# PowerMonitorV2.net
KiCad netlist of a schematic drawn in EAGLE
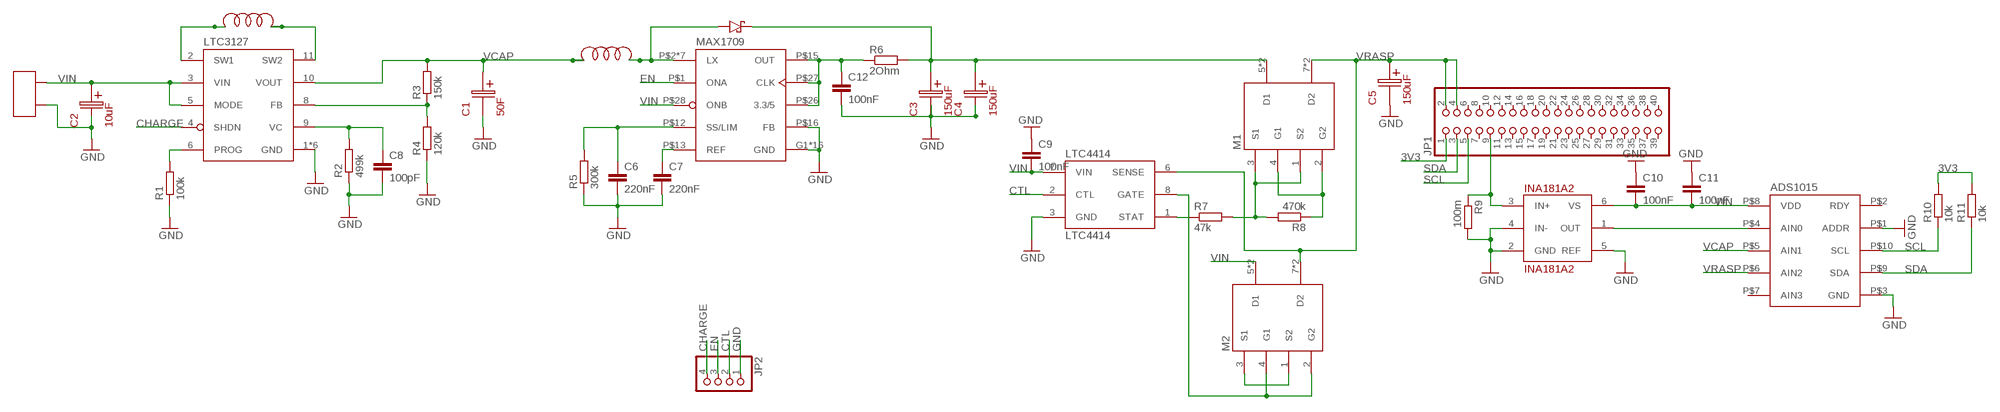
[diagram p0: schematic, sheet 1]

(export (version "E")
  (design (tool "Eeschema 10.0.6"))
  (components
    (comp (ref "ADS1015")
      (value "ADS1015")
      (footprint "eagle-import:VSSOP-10")
      (libsource (lib "eagle-import") (part "ADS1015"))
    )
    (comp (ref "C1")
      (value "50F")
      (footprint "eagle-import:CAP_RAD_8MM")
      (libsource (lib "eagle-import") (part "CAPACITOR8MM50F_SUPERCAP"))
    )
    (comp (ref "C2")
      (value "10uF")
      (footprint "eagle-import:CAP_RAD_2.5MM")
      (libsource (lib "eagle-import") (part "CAPACITOR2.5MM"))
    )
    (comp (ref "C3")
      (value "150uF")
      (footprint "eagle-import:CAP_RAD_3.5MM")
      (libsource (lib "eagle-import") (part "CAPACITOR3.5MM"))
    )
    (comp (ref "C4")
      (value "150uF")
      (footprint "eagle-import:CAP_RAD_3.5MM")
      (libsource (lib "eagle-import") (part "CAPACITOR3.5MM"))
    )
    (comp (ref "C5")
      (value "150uF")
      (footprint "eagle-import:CAP_RAD_3.5MM")
      (libsource (lib "eagle-import") (part "CAPACITOR3.5MM"))
    )
    (comp (ref "C6")
      (value "220nF")
      (footprint "eagle-import:C0805")
      (libsource (lib "eagle-import") (part "C-EUC0805"))
    )
    (comp (ref "C7")
      (value "220nF")
      (footprint "eagle-import:C0805")
      (libsource (lib "eagle-import") (part "C-EUC0805"))
    )
    (comp (ref "C8")
      (value "100pF")
      (footprint "eagle-import:C0805")
      (libsource (lib "eagle-import") (part "C-EUC0805"))
    )
    (comp (ref "C9")
      (value "100nF")
      (footprint "eagle-import:C0805")
      (libsource (lib "eagle-import") (part "C-EUC0805"))
    )
    (comp (ref "C10")
      (value "100nF")
      (footprint "eagle-import:C0805")
      (libsource (lib "eagle-import") (part "C-EUC0805"))
    )
    (comp (ref "C11")
      (value "100nF")
      (footprint "eagle-import:C0805")
      (libsource (lib "eagle-import") (part "C-EUC0805"))
    )
    (comp (ref "C12")
      (value "100nF")
      (footprint "eagle-import:C0805")
      (libsource (lib "eagle-import") (part "C-EUC0805"))
    )
    (comp (ref "CON1")
      (value "TERM-2")
      (footprint "eagle-import:TERM-2")
      (libsource (lib "eagle-import") (part "TERM-2"))
    )
    (comp (ref "D1")
      (value "STPS8L30_DPAK")
      (footprint "eagle-import:DPAK")
      (libsource (lib "eagle-import") (part "STPS8L30_DPAK"))
    )
    (comp (ref "INA181A2")
      (value "INA181A2")
      (footprint "eagle-import:SOT-23-6")
      (libsource (lib "eagle-import") (part "INA181A2"))
    )
    (comp (ref "JP1")
      (value "PINHD-2X20")
      (footprint "eagle-import:2X20")
      (libsource (lib "eagle-import") (part "PINHD-2X20"))
    )
    (comp (ref "JP2")
      (value "PINHD-1X4/90")
      (footprint "eagle-import:1X04_90")
      (libsource (lib "eagle-import") (part "PINHD-1X4/90"))
    )
    (comp (ref "L1")
      (value "4.7uH")
      (footprint "eagle-import:IND6X6")
      (libsource (lib "eagle-import") (part "INDUCTOR6MM"))
    )
    (comp (ref "L2")
      (value "1uH")
      (footprint "eagle-import:IND6X6")
      (libsource (lib "eagle-import") (part "INDUCTOR6MM"))
    )
    (comp (ref "LTC3127")
      (value "LTC3127")
      (footprint "eagle-import:MS-12E2")
      (libsource (lib "eagle-import") (part "LTC3127"))
    )
    (comp (ref "LTC4414")
      (value "LTC4414")
      (footprint "eagle-import:MS8")
      (libsource (lib "eagle-import") (part "LTC4414"))
    )
    (comp (ref "M1")
      (value "IRF9358PBF")
      (footprint "eagle-import:SO-8")
      (libsource (lib "eagle-import") (part "IRF9358PBF"))
    )
    (comp (ref "M2")
      (value "IRF9358PBF")
      (footprint "eagle-import:SO-8")
      (libsource (lib "eagle-import") (part "IRF9358PBF"))
    )
    (comp (ref "MAX1709")
      (value "MAX1709")
      (footprint "eagle-import:TSSOP-EP28")
      (libsource (lib "eagle-import") (part "MAX1709"))
    )
    (comp (ref "R1")
      (value "100k")
      (footprint "eagle-import:R0805")
      (libsource (lib "eagle-import") (part "R-EU_R0805"))
    )
    (comp (ref "R2")
      (value "499k")
      (footprint "eagle-import:R0805")
      (libsource (lib "eagle-import") (part "R-EU_R0805"))
    )
    (comp (ref "R3")
      (value "150k")
      (footprint "eagle-import:R0805")
      (libsource (lib "eagle-import") (part "R-EU_R0805"))
    )
    (comp (ref "R4")
      (value "120k")
      (footprint "eagle-import:R0805")
      (libsource (lib "eagle-import") (part "R-EU_R0805"))
    )
    (comp (ref "R5")
      (value "300k")
      (footprint "eagle-import:R0805")
      (libsource (lib "eagle-import") (part "R-EU_R0805"))
    )
    (comp (ref "R6")
      (value "2Ohm")
      (footprint "eagle-import:R0805")
      (libsource (lib "eagle-import") (part "R-EU_R0805"))
    )
    (comp (ref "R7")
      (value "47k")
      (footprint "eagle-import:R0805")
      (libsource (lib "eagle-import") (part "R-EU_R0805"))
    )
    (comp (ref "R8")
      (value "470k")
      (footprint "eagle-import:R0805")
      (libsource (lib "eagle-import") (part "R-EU_R0805"))
    )
    (comp (ref "R9")
      (value "100m")
      (footprint "eagle-import:R0805")
      (libsource (lib "eagle-import") (part "R-EU_R0805"))
    )
    (comp (ref "R10")
      (value "10k")
      (footprint "eagle-import:R0805")
      (libsource (lib "eagle-import") (part "R-EU_R0805"))
    )
    (comp (ref "R11")
      (value "10k")
      (footprint "eagle-import:R0805")
      (libsource (lib "eagle-import") (part "R-EU_R0805"))
    )
  )
  (nets
    (net (code "1") (name "/3V3") (class "Default")
      (node (ref "JP1") (pin "1") (pinfunction "1_1") (pintype "passive"))
      (node (ref "R10") (pin "2") (pinfunction "2_2") (pintype "passive"))
      (node (ref "R11") (pin "2") (pinfunction "2_2") (pintype "passive"))
    )
    (net (code "2") (name "/CHARGE") (class "Default")
      (node (ref "JP2") (pin "4") (pinfunction "4_4") (pintype "passive"))
      (node (ref "LTC3127") (pin "4") (pinfunction "SHDN_4") (pintype "bidirectional"))
    )
    (net (code "3") (name "/CTL") (class "Default")
      (node (ref "JP2") (pin "2") (pinfunction "2_2") (pintype "passive"))
      (node (ref "LTC4414") (pin "2") (pinfunction "CTL_2") (pintype "bidirectional"))
    )
    (net (code "4") (name "/EN") (class "Default")
      (node (ref "JP2") (pin "3") (pinfunction "3_3") (pintype "passive"))
      (node (ref "MAX1709") (pin "P$1") (pinfunction "ONA_P$1") (pintype "bidirectional"))
    )
    (net (code "5") (name "/SCL") (class "Default")
      (node (ref "ADS1015") (pin "P$10") (pinfunction "SCL_P$10") (pintype "bidirectional"))
      (node (ref "JP1") (pin "5") (pinfunction "5_5") (pintype "passive"))
      (node (ref "R10") (pin "1") (pinfunction "1_1") (pintype "passive"))
    )
    (net (code "6") (name "/SDA") (class "Default")
      (node (ref "ADS1015") (pin "P$9") (pinfunction "SDA_P$9") (pintype "bidirectional"))
      (node (ref "JP1") (pin "3") (pinfunction "3_3") (pintype "passive"))
      (node (ref "R11") (pin "1") (pinfunction "1_1") (pintype "passive"))
    )
    (net (code "7") (name "/VCAP") (class "Default")
      (node (ref "ADS1015") (pin "P$5") (pinfunction "AIN1_P$5") (pintype "bidirectional"))
      (node (ref "C1") (pin "VCAP") (pinfunction "V+_VCAP") (pintype "power_in"))
      (node (ref "L2") (pin "P$1") (pinfunction "P$1_P$1") (pintype "bidirectional"))
      (node (ref "L2") (pin "P$3") (pinfunction "P$1_P$3") (pintype "bidirectional"))
      (node (ref "L2") (pin "P$4") (pinfunction "P$1_P$4") (pintype "bidirectional"))
      (node (ref "LTC3127") (pin "10") (pinfunction "VOUT_10") (pintype "bidirectional"))
      (node (ref "R3") (pin "2") (pinfunction "2_2") (pintype "passive"))
    )
    (net (code "8") (name "/VIN") (class "Default")
      (node (ref "ADS1015") (pin "P$8") (pinfunction "VDD_P$8") (pintype "bidirectional"))
      (node (ref "C10") (pin "2") (pinfunction "2_2") (pintype "passive"))
      (node (ref "C11") (pin "2") (pinfunction "2_2") (pintype "passive"))
      (node (ref "C2") (pin "VCAP") (pinfunction "V+_VCAP") (pintype "power_in"))
      (node (ref "C9") (pin "2") (pinfunction "2_2") (pintype "passive"))
      (node (ref "CON1") (pin "1") (pinfunction "P$1_1") (pintype "bidirectional"))
      (node (ref "INA181A2") (pin "6") (pinfunction "VS_6") (pintype "power_in"))
      (node (ref "LTC3127") (pin "3") (pinfunction "VIN_3") (pintype "bidirectional"))
      (node (ref "LTC3127") (pin "5") (pinfunction "MODE_5") (pintype "bidirectional"))
      (node (ref "LTC4414") (pin "7") (pinfunction "VIN_7") (pintype "bidirectional"))
      (node (ref "M2") (pin "5") (pinfunction "D1_5") (pintype "bidirectional"))
      (node (ref "M2") (pin "6") (pinfunction "D1_6") (pintype "bidirectional"))
      (node (ref "MAX1709") (pin "P$28") (pinfunction "ONB_P$28") (pintype "bidirectional"))
    )
    (net (code "9") (name "/VRASP") (class "Default")
      (node (ref "ADS1015") (pin "P$6") (pinfunction "AIN2_P$6") (pintype "bidirectional"))
      (node (ref "C5") (pin "VCAP") (pinfunction "V+_VCAP") (pintype "power_in"))
      (node (ref "JP1") (pin "2") (pinfunction "2_2") (pintype "passive"))
      (node (ref "JP1") (pin "4") (pinfunction "4_4") (pintype "passive"))
      (node (ref "LTC4414") (pin "6") (pinfunction "SENSE_6") (pintype "bidirectional"))
      (node (ref "M1") (pin "7") (pinfunction "D2_7") (pintype "bidirectional"))
      (node (ref "M1") (pin "8") (pinfunction "D2_8") (pintype "bidirectional"))
      (node (ref "M2") (pin "7") (pinfunction "D2_7") (pintype "bidirectional"))
      (node (ref "M2") (pin "8") (pinfunction "D2_8") (pintype "bidirectional"))
    )
    (net (code "10") (name "GND") (class "Default")
      (node (ref "ADS1015") (pin "P$1") (pinfunction "ADDR_P$1") (pintype "bidirectional"))
      (node (ref "ADS1015") (pin "P$3") (pinfunction "GND_P$3") (pintype "bidirectional"))
      (node (ref "C1") (pin "GND") (pinfunction "V-_GND") (pintype "power_in"))
      (node (ref "C10") (pin "1") (pinfunction "1_1") (pintype "passive"))
      (node (ref "C11") (pin "1") (pinfunction "1_1") (pintype "passive"))
      (node (ref "C12") (pin "2") (pinfunction "2_2") (pintype "passive"))
      (node (ref "C2") (pin "GND") (pinfunction "V-_GND") (pintype "power_in"))
      (node (ref "C3") (pin "GND") (pinfunction "V-_GND") (pintype "power_in"))
      (node (ref "C4") (pin "GND") (pinfunction "V-_GND") (pintype "power_in"))
      (node (ref "C5") (pin "GND") (pinfunction "V-_GND") (pintype "power_in"))
      (node (ref "C6") (pin "2") (pinfunction "2_2") (pintype "passive"))
      (node (ref "C7") (pin "2") (pinfunction "2_2") (pintype "passive"))
      (node (ref "C8") (pin "2") (pinfunction "2_2") (pintype "passive"))
      (node (ref "C9") (pin "1") (pinfunction "1_1") (pintype "passive"))
      (node (ref "CON1") (pin "2") (pinfunction "P$2_2") (pintype "bidirectional"))
      (node (ref "INA181A2") (pin "2") (pinfunction "GND_2") (pintype "power_in"))
      (node (ref "INA181A2") (pin "4") (pinfunction "IN-_4") (pintype "input"))
      (node (ref "INA181A2") (pin "5") (pinfunction "REF_5") (pintype "input"))
      (node (ref "JP2") (pin "1") (pinfunction "1_1") (pintype "passive"))
      (node (ref "LTC3127") (pin "1") (pinfunction "GND_1") (pintype "bidirectional"))
      (node (ref "LTC3127") (pin "12") (pinfunction "GND_12") (pintype "bidirectional"))
      (node (ref "LTC3127") (pin "13_0") (pinfunction "GND_13_0") (pintype "bidirectional"))
      (node (ref "LTC3127") (pin "13_1") (pinfunction "GND_13_1") (pintype "bidirectional"))
      (node (ref "LTC3127") (pin "13_2") (pinfunction "GND_13_2") (pintype "bidirectional"))
      (node (ref "LTC3127") (pin "7") (pinfunction "GND_7") (pintype "bidirectional"))
      (node (ref "LTC4414") (pin "3") (pinfunction "GND_3") (pintype "bidirectional"))
      (node (ref "MAX1709") (pin "G1") (pinfunction "GND_G1") (pintype "bidirectional"))
      (node (ref "MAX1709") (pin "G2") (pinfunction "GND_G2") (pintype "bidirectional"))
      (node (ref "MAX1709") (pin "G3") (pinfunction "GND_G3") (pintype "bidirectional"))
      (node (ref "MAX1709") (pin "G4") (pinfunction "GND_G4") (pintype "bidirectional"))
      (node (ref "MAX1709") (pin "G5") (pinfunction "GND_G5") (pintype "bidirectional"))
      (node (ref "MAX1709") (pin "G6") (pinfunction "GND_G6") (pintype "bidirectional"))
      (node (ref "MAX1709") (pin "G7") (pinfunction "GND_G7") (pintype "bidirectional"))
      (node (ref "MAX1709") (pin "G8") (pinfunction "GND_G8") (pintype "bidirectional"))
      (node (ref "MAX1709") (pin "P$11") (pinfunction "GND_P$11") (pintype "bidirectional"))
      (node (ref "MAX1709") (pin "P$14") (pinfunction "GND_P$14") (pintype "bidirectional"))
      (node (ref "MAX1709") (pin "P$16") (pinfunction "FB_P$16") (pintype "bidirectional"))
      (node (ref "MAX1709") (pin "P$18") (pinfunction "GND_P$18") (pintype "bidirectional"))
      (node (ref "MAX1709") (pin "P$19") (pinfunction "GND_P$19") (pintype "bidirectional"))
      (node (ref "MAX1709") (pin "P$20") (pinfunction "GND_P$20") (pintype "bidirectional"))
      (node (ref "MAX1709") (pin "P$21") (pinfunction "GND_P$21") (pintype "bidirectional"))
      (node (ref "MAX1709") (pin "P$22") (pinfunction "GND_P$22") (pintype "bidirectional"))
      (node (ref "MAX1709") (pin "P$23") (pinfunction "GND_P$23") (pintype "bidirectional"))
      (node (ref "R1") (pin "1") (pinfunction "1_1") (pintype "passive"))
      (node (ref "R2") (pin "1") (pinfunction "1_1") (pintype "passive"))
      (node (ref "R4") (pin "1") (pinfunction "1_1") (pintype "passive"))
      (node (ref "R5") (pin "1") (pinfunction "1_1") (pintype "passive"))
      (node (ref "R9") (pin "2") (pinfunction "2_2") (pintype "passive"))
    )
    (net (code "11") (name "Net-(ADS1015-AIN0)") (class "Default")
      (node (ref "ADS1015") (pin "P$4") (pinfunction "AIN0_P$4") (pintype "bidirectional"))
      (node (ref "INA181A2") (pin "1") (pinfunction "OUT_1") (pintype "output"))
    )
    (net (code "12") (name "Net-(C3-V+)") (class "Default")
      (node (ref "C3") (pin "VCAP") (pinfunction "V+_VCAP") (pintype "power_in"))
      (node (ref "C4") (pin "VCAP") (pinfunction "V+_VCAP") (pintype "power_in"))
      (node (ref "D1") (pin "P$1") (pinfunction "CATHODE_P$1") (pintype "bidirectional"))
      (node (ref "D1") (pin "P$1_0") (pinfunction "CATHODE_P$1_0") (pintype "bidirectional"))
      (node (ref "D1") (pin "P$1_1") (pinfunction "CATHODE_P$1_1") (pintype "bidirectional"))
      (node (ref "D1") (pin "P$1_2") (pinfunction "CATHODE_P$1_2") (pintype "bidirectional"))
      (node (ref "D1") (pin "P$1_3") (pinfunction "CATHODE_P$1_3") (pintype "bidirectional"))
      (node (ref "D1") (pin "P$1_4") (pinfunction "CATHODE_P$1_4") (pintype "bidirectional"))
      (node (ref "D1") (pin "P$1_5") (pinfunction "CATHODE_P$1_5") (pintype "bidirectional"))
      (node (ref "D1") (pin "P$1_6") (pinfunction "CATHODE_P$1_6") (pintype "bidirectional"))
      (node (ref "D1") (pin "P$1_7") (pinfunction "CATHODE_P$1_7") (pintype "bidirectional"))
      (node (ref "D1") (pin "P$1_8") (pinfunction "CATHODE_P$1_8") (pintype "bidirectional"))
      (node (ref "D1") (pin "P$1_9") (pinfunction "CATHODE_P$1_9") (pintype "bidirectional"))
      (node (ref "M1") (pin "5") (pinfunction "D1_5") (pintype "bidirectional"))
      (node (ref "M1") (pin "6") (pinfunction "D1_6") (pintype "bidirectional"))
      (node (ref "R6") (pin "2") (pinfunction "2_2") (pintype "passive"))
    )
    (net (code "13") (name "Net-(D1-ANODE)") (class "Default")
      (node (ref "D1") (pin "P$2") (pinfunction "ANODE_P$2") (pintype "bidirectional"))
      (node (ref "L2") (pin "P$2") (pinfunction "P$2_P$2") (pintype "bidirectional"))
      (node (ref "L2") (pin "P$5") (pinfunction "P$2_P$5") (pintype "bidirectional"))
      (node (ref "L2") (pin "P$6") (pinfunction "P$2_P$6") (pintype "bidirectional"))
      (node (ref "MAX1709") (pin "P$2") (pinfunction "LX_P$2") (pintype "bidirectional"))
      (node (ref "MAX1709") (pin "P$3") (pinfunction "LX_P$3") (pintype "bidirectional"))
      (node (ref "MAX1709") (pin "P$4") (pinfunction "LX_P$4") (pintype "bidirectional"))
      (node (ref "MAX1709") (pin "P$5") (pinfunction "LX_P$5") (pintype "bidirectional"))
      (node (ref "MAX1709") (pin "P$6") (pinfunction "LX_P$6") (pintype "bidirectional"))
      (node (ref "MAX1709") (pin "P$7") (pinfunction "LX_P$7") (pintype "bidirectional"))
      (node (ref "MAX1709") (pin "P$8") (pinfunction "LX_P$8") (pintype "bidirectional"))
    )
    (net (code "14") (name "Net-(INA181A2-IN+)") (class "Default")
      (node (ref "INA181A2") (pin "3") (pinfunction "IN+_3") (pintype "input"))
      (node (ref "JP1") (pin "9") (pinfunction "9_9") (pintype "passive"))
      (node (ref "R9") (pin "1") (pinfunction "1_1") (pintype "passive"))
    )
    (net (code "15") (name "Net-(LTC3127-FB)") (class "Default")
      (node (ref "LTC3127") (pin "8") (pinfunction "FB_8") (pintype "bidirectional"))
      (node (ref "R3") (pin "1") (pinfunction "1_1") (pintype "passive"))
      (node (ref "R4") (pin "2") (pinfunction "2_2") (pintype "passive"))
    )
    (net (code "16") (name "Net-(LTC3127-PROG)") (class "Default")
      (node (ref "LTC3127") (pin "6") (pinfunction "PROG_6") (pintype "bidirectional"))
      (node (ref "R1") (pin "2") (pinfunction "2_2") (pintype "passive"))
    )
    (net (code "17") (name "Net-(LTC3127-SW1)") (class "Default")
      (node (ref "L1") (pin "P$1") (pinfunction "P$1_P$1") (pintype "bidirectional"))
      (node (ref "L1") (pin "P$3") (pinfunction "P$1_P$3") (pintype "bidirectional"))
      (node (ref "L1") (pin "P$4") (pinfunction "P$1_P$4") (pintype "bidirectional"))
      (node (ref "LTC3127") (pin "2") (pinfunction "SW1_2") (pintype "bidirectional"))
    )
    (net (code "18") (name "Net-(LTC3127-SW2)") (class "Default")
      (node (ref "L1") (pin "P$2") (pinfunction "P$2_P$2") (pintype "bidirectional"))
      (node (ref "L1") (pin "P$5") (pinfunction "P$2_P$5") (pintype "bidirectional"))
      (node (ref "L1") (pin "P$6") (pinfunction "P$2_P$6") (pintype "bidirectional"))
      (node (ref "LTC3127") (pin "11") (pinfunction "SW2_11") (pintype "bidirectional"))
    )
    (net (code "19") (name "Net-(LTC3127-VC)") (class "Default")
      (node (ref "C8") (pin "1") (pinfunction "1_1") (pintype "passive"))
      (node (ref "LTC3127") (pin "9") (pinfunction "VC_9") (pintype "bidirectional"))
      (node (ref "R2") (pin "2") (pinfunction "2_2") (pintype "passive"))
    )
    (net (code "20") (name "Net-(LTC4414-GATE)") (class "Default")
      (node (ref "LTC4414") (pin "8") (pinfunction "GATE_8") (pintype "bidirectional"))
      (node (ref "M2") (pin "2") (pinfunction "G2_2") (pintype "bidirectional"))
      (node (ref "M2") (pin "4") (pinfunction "G1_4") (pintype "bidirectional"))
    )
    (net (code "21") (name "Net-(LTC4414-STAT)") (class "Default")
      (node (ref "LTC4414") (pin "1") (pinfunction "STAT_1") (pintype "bidirectional"))
      (node (ref "R7") (pin "1") (pinfunction "1_1") (pintype "passive"))
    )
    (net (code "22") (name "Net-(M1-G1)") (class "Default")
      (node (ref "M1") (pin "2") (pinfunction "G2_2") (pintype "bidirectional"))
      (node (ref "M1") (pin "4") (pinfunction "G1_4") (pintype "bidirectional"))
      (node (ref "R8") (pin "1") (pinfunction "1_1") (pintype "passive"))
    )
    (net (code "23") (name "Net-(M1-S1)") (class "Default")
      (node (ref "M1") (pin "1") (pinfunction "S2_1") (pintype "bidirectional"))
      (node (ref "M1") (pin "3") (pinfunction "S1_3") (pintype "bidirectional"))
      (node (ref "R7") (pin "2") (pinfunction "2_2") (pintype "passive"))
      (node (ref "R8") (pin "2") (pinfunction "2_2") (pintype "passive"))
    )
    (net (code "24") (name "Net-(M2-S1)") (class "Default")
      (node (ref "M2") (pin "1") (pinfunction "S2_1") (pintype "bidirectional"))
      (node (ref "M2") (pin "3") (pinfunction "S1_3") (pintype "bidirectional"))
    )
    (net (code "25") (name "Net-(MAX1709-3.3{slash}5)") (class "Default")
      (node (ref "C12") (pin "1") (pinfunction "1_1") (pintype "passive"))
      (node (ref "MAX1709") (pin "P$15") (pinfunction "OUT_P$15") (pintype "bidirectional"))
      (node (ref "MAX1709") (pin "P$26") (pinfunction "3.3/5_P$26") (pintype "bidirectional"))
      (node (ref "MAX1709") (pin "P$27") (pinfunction "CLK_P$27") (pintype "bidirectional"))
      (node (ref "R6") (pin "1") (pinfunction "1_1") (pintype "passive"))
    )
    (net (code "26") (name "Net-(MAX1709-REF)") (class "Default")
      (node (ref "C7") (pin "1") (pinfunction "1_1") (pintype "passive"))
      (node (ref "MAX1709") (pin "P$13") (pinfunction "REF_P$13") (pintype "bidirectional"))
    )
    (net (code "27") (name "Net-(MAX1709-SS{slash}LIM)") (class "Default")
      (node (ref "C6") (pin "1") (pinfunction "1_1") (pintype "passive"))
      (node (ref "MAX1709") (pin "P$12") (pinfunction "SS/LIM_P$12") (pintype "bidirectional"))
      (node (ref "R5") (pin "2") (pinfunction "2_2") (pintype "passive"))
    )
    (net (code "28") (name "unconnected-(ADS1015-AIN3-PadP$7)") (class "Default")
      (node (ref "ADS1015") (pin "P$7") (pinfunction "AIN3_P$7") (pintype "bidirectional"))
    )
    (net (code "29") (name "unconnected-(ADS1015-RDY-PadP$2)") (class "Default")
      (node (ref "ADS1015") (pin "P$2") (pinfunction "RDY_P$2") (pintype "bidirectional"))
    )
    (net (code "30") (name "unconnected-(JP1-Pad6)") (class "Default")
      (node (ref "JP1") (pin "6") (pinfunction "6_6") (pintype "passive"))
    )
    (net (code "31") (name "unconnected-(JP1-Pad7)") (class "Default")
      (node (ref "JP1") (pin "7") (pinfunction "7_7") (pintype "passive"))
    )
    (net (code "32") (name "unconnected-(JP1-Pad8)") (class "Default")
      (node (ref "JP1") (pin "8") (pinfunction "8_8") (pintype "passive"))
    )
    (net (code "33") (name "unconnected-(JP1-Pad10)") (class "Default")
      (node (ref "JP1") (pin "10") (pinfunction "10_10") (pintype "passive"))
    )
    (net (code "34") (name "unconnected-(JP1-Pad11)") (class "Default")
      (node (ref "JP1") (pin "11") (pinfunction "11_11") (pintype "passive"))
    )
    (net (code "35") (name "unconnected-(JP1-Pad12)") (class "Default")
      (node (ref "JP1") (pin "12") (pinfunction "12_12") (pintype "passive"))
    )
    (net (code "36") (name "unconnected-(JP1-Pad13)") (class "Default")
      (node (ref "JP1") (pin "13") (pinfunction "13_13") (pintype "passive"))
    )
    (net (code "37") (name "unconnected-(JP1-Pad14)") (class "Default")
      (node (ref "JP1") (pin "14") (pinfunction "14_14") (pintype "passive"))
    )
    (net (code "38") (name "unconnected-(JP1-Pad15)") (class "Default")
      (node (ref "JP1") (pin "15") (pinfunction "15_15") (pintype "passive"))
    )
    (net (code "39") (name "unconnected-(JP1-Pad16)") (class "Default")
      (node (ref "JP1") (pin "16") (pinfunction "16_16") (pintype "passive"))
    )
    (net (code "40") (name "unconnected-(JP1-Pad17)") (class "Default")
      (node (ref "JP1") (pin "17") (pinfunction "17_17") (pintype "passive"))
    )
    (net (code "41") (name "unconnected-(JP1-Pad18)") (class "Default")
      (node (ref "JP1") (pin "18") (pinfunction "18_18") (pintype "passive"))
    )
    (net (code "42") (name "unconnected-(JP1-Pad19)") (class "Default")
      (node (ref "JP1") (pin "19") (pinfunction "19_19") (pintype "passive"))
    )
    (net (code "43") (name "unconnected-(JP1-Pad20)") (class "Default")
      (node (ref "JP1") (pin "20") (pinfunction "20_20") (pintype "passive"))
    )
    (net (code "44") (name "unconnected-(JP1-Pad21)") (class "Default")
      (node (ref "JP1") (pin "21") (pinfunction "21_21") (pintype "passive"))
    )
    (net (code "45") (name "unconnected-(JP1-Pad22)") (class "Default")
      (node (ref "JP1") (pin "22") (pinfunction "22_22") (pintype "passive"))
    )
    (net (code "46") (name "unconnected-(JP1-Pad23)") (class "Default")
      (node (ref "JP1") (pin "23") (pinfunction "23_23") (pintype "passive"))
    )
    (net (code "47") (name "unconnected-(JP1-Pad24)") (class "Default")
      (node (ref "JP1") (pin "24") (pinfunction "24_24") (pintype "passive"))
    )
    (net (code "48") (name "unconnected-(JP1-Pad25)") (class "Default")
      (node (ref "JP1") (pin "25") (pinfunction "25_25") (pintype "passive"))
    )
    (net (code "49") (name "unconnected-(JP1-Pad26)") (class "Default")
      (node (ref "JP1") (pin "26") (pinfunction "26_26") (pintype "passive"))
    )
    (net (code "50") (name "unconnected-(JP1-Pad27)") (class "Default")
      (node (ref "JP1") (pin "27") (pinfunction "27_27") (pintype "passive"))
    )
    (net (code "51") (name "unconnected-(JP1-Pad28)") (class "Default")
      (node (ref "JP1") (pin "28") (pinfunction "28_28") (pintype "passive"))
    )
    (net (code "52") (name "unconnected-(JP1-Pad29)") (class "Default")
      (node (ref "JP1") (pin "29") (pinfunction "29_29") (pintype "passive"))
    )
    (net (code "53") (name "unconnected-(JP1-Pad30)") (class "Default")
      (node (ref "JP1") (pin "30") (pinfunction "30_30") (pintype "passive"))
    )
    (net (code "54") (name "unconnected-(JP1-Pad31)") (class "Default")
      (node (ref "JP1") (pin "31") (pinfunction "31_31") (pintype "passive"))
    )
    (net (code "55") (name "unconnected-(JP1-Pad32)") (class "Default")
      (node (ref "JP1") (pin "32") (pinfunction "32_32") (pintype "passive"))
    )
    (net (code "56") (name "unconnected-(JP1-Pad33)") (class "Default")
      (node (ref "JP1") (pin "33") (pinfunction "33_33") (pintype "passive"))
    )
    (net (code "57") (name "unconnected-(JP1-Pad34)") (class "Default")
      (node (ref "JP1") (pin "34") (pinfunction "34_34") (pintype "passive"))
    )
    (net (code "58") (name "unconnected-(JP1-Pad35)") (class "Default")
      (node (ref "JP1") (pin "35") (pinfunction "35_35") (pintype "passive"))
    )
    (net (code "59") (name "unconnected-(JP1-Pad36)") (class "Default")
      (node (ref "JP1") (pin "36") (pinfunction "36_36") (pintype "passive"))
    )
    (net (code "60") (name "unconnected-(JP1-Pad37)") (class "Default")
      (node (ref "JP1") (pin "37") (pinfunction "37_37") (pintype "passive"))
    )
    (net (code "61") (name "unconnected-(JP1-Pad38)") (class "Default")
      (node (ref "JP1") (pin "38") (pinfunction "38_38") (pintype "passive"))
    )
    (net (code "62") (name "unconnected-(JP1-Pad39)") (class "Default")
      (node (ref "JP1") (pin "39") (pinfunction "39_39") (pintype "passive"))
    )
    (net (code "63") (name "unconnected-(JP1-Pad40)") (class "Default")
      (node (ref "JP1") (pin "40") (pinfunction "40_40") (pintype "passive"))
    )
  )
)
